# Sensors.net
KiCad netlist of a schematic drawn in Altium Designer
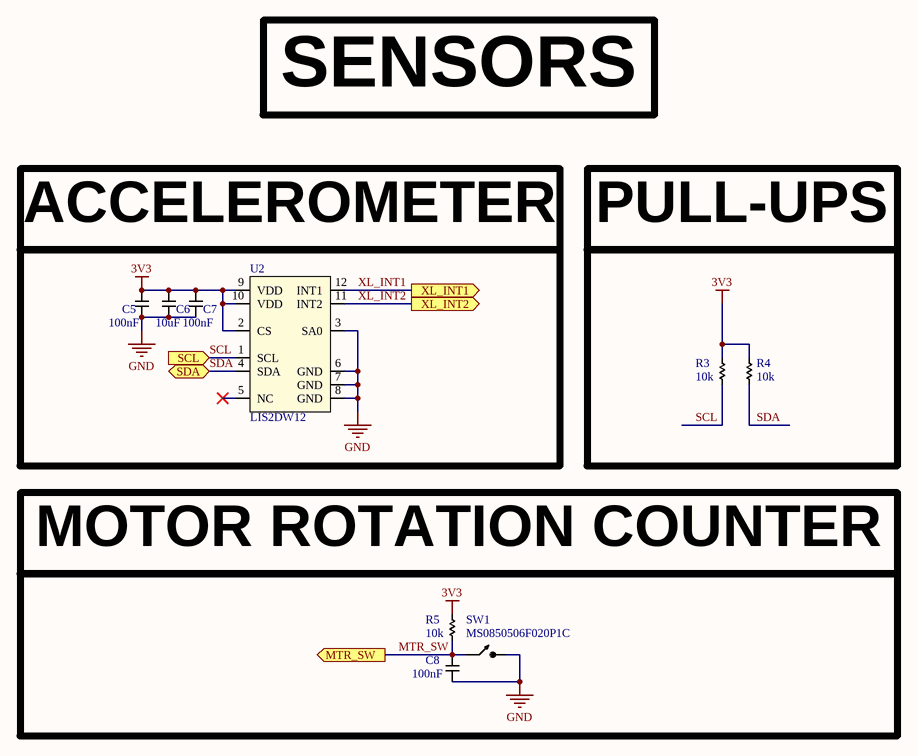
[diagram p0: Sensors.SchDoc]

(export (version "E")
  (design (tool "Eeschema 10.0.6"))
  (components
    (comp (ref "C5")
      (value "100nF")
      (footprint "CAP_0402_HIGH")
      (description "0402 Capacitor")
      (libsource (lib "smLib") (part "Capacitor_0402"))
    )
    (comp (ref "C6")
      (value "10uF")
      (footprint "CAP_0603_HIGH")
      (description "0603 Capacitor")
      (libsource (lib "smLib") (part "Capacitor_0603"))
    )
    (comp (ref "C7")
      (value "100nF")
      (footprint "CAP_0402_HIGH")
      (description "0402 Capacitor")
      (libsource (lib "smLib") (part "Capacitor_0402"))
    )
    (comp (ref "C8")
      (value "100nF")
      (footprint "CAP_0402_HIGH")
      (description "0402 Capacitor")
      (libsource (lib "smLib") (part "Capacitor_0402"))
    )
    (comp (ref "R3")
      (value "10k")
      (footprint "RES_0402_HIGH")
      (description "0402 Resistor")
      (libsource (lib "smLib") (part "Resistor_0402"))
    )
    (comp (ref "R4")
      (value "10k")
      (footprint "RES_0402_HIGH")
      (description "0402 Resistor")
      (libsource (lib "smLib") (part "Resistor_0402"))
    )
    (comp (ref "R5")
      (value "10k")
      (footprint "RES_0402_HIGH")
      (description "0402 Resistor")
      (libsource (lib "smLib") (part "Resistor_0402"))
    )
    (comp (ref "SW1")
      (value "MS0850506F020P1C")
      (footprint "MS0850506F020P1C")
      (description "MS0850506F020P1C SWITCH SNAP ACT SPST-NO 5A 125V")
      (libsource (lib "smLib") (part "MS0850506F020P1C"))
    )
    (comp (ref "U2")
      (value "LIS2DW12")
      (footprint "LIS2DW12")
      (description "LIS2DW12 Accelerometer X, Y, Z Axis ±2g, 4g, 8g, 16g 400Hz 12-LGA (2x2)")
      (libsource (lib "smLib") (part "LIS2DW12"))
    )
  )
  (nets
    (net (code "1") (name "/MTR_SW") (class "Default")
      (node (ref "C8") (pin "2") (pinfunction "2_2") (pintype "passive"))
      (node (ref "R5") (pin "1") (pinfunction "1_1") (pintype "passive"))
      (node (ref "SW1") (pin "1") (pinfunction "1_1") (pintype "passive"))
    )
    (net (code "2") (name "/SCL") (class "Default")
      (node (ref "R3") (pin "1") (pinfunction "1_1") (pintype "passive"))
      (node (ref "U2") (pin "1") (pinfunction "SCL_1") (pintype "passive"))
    )
    (net (code "3") (name "/SDA") (class "Default")
      (node (ref "R4") (pin "1") (pinfunction "1_1") (pintype "passive"))
      (node (ref "U2") (pin "4") (pinfunction "SDA_4") (pintype "passive"))
    )
    (net (code "4") (name "/XL_INT1") (class "Default")
      (node (ref "U2") (pin "12") (pinfunction "INT1_12") (pintype "passive"))
    )
    (net (code "5") (name "/XL_INT2") (class "Default")
      (node (ref "U2") (pin "11") (pinfunction "INT2_11") (pintype "passive"))
    )
    (net (code "6") (name "3V3") (class "Default")
      (node (ref "C5") (pin "2") (pinfunction "2_2") (pintype "passive"))
      (node (ref "C6") (pin "2") (pinfunction "2_2") (pintype "passive"))
      (node (ref "C7") (pin "2") (pinfunction "2_2") (pintype "passive"))
      (node (ref "R3") (pin "2") (pinfunction "2_2") (pintype "passive"))
      (node (ref "R4") (pin "2") (pinfunction "2_2") (pintype "passive"))
      (node (ref "R5") (pin "2") (pinfunction "2_2") (pintype "passive"))
      (node (ref "U2") (pin "10") (pinfunction "VDD_10") (pintype "passive"))
      (node (ref "U2") (pin "2") (pinfunction "CS_2") (pintype "passive"))
      (node (ref "U2") (pin "9") (pinfunction "VDD_9") (pintype "passive"))
    )
    (net (code "7") (name "GND") (class "Default")
      (node (ref "C5") (pin "1") (pinfunction "1_1") (pintype "passive"))
      (node (ref "C6") (pin "1") (pinfunction "1_1") (pintype "passive"))
      (node (ref "C7") (pin "1") (pinfunction "1_1") (pintype "passive"))
      (node (ref "C8") (pin "1") (pinfunction "1_1") (pintype "passive"))
      (node (ref "SW1") (pin "2") (pinfunction "2_2") (pintype "passive"))
      (node (ref "U2") (pin "3") (pinfunction "SA0_3") (pintype "passive"))
      (node (ref "U2") (pin "6") (pinfunction "GND_6") (pintype "passive"))
      (node (ref "U2") (pin "7") (pinfunction "GND_7") (pintype "passive"))
      (node (ref "U2") (pin "8") (pinfunction "GND_8") (pintype "passive"))
    )
    (net (code "8") (name "unconnected-(U2-NC-Pad5)") (class "Default")
      (node (ref "U2") (pin "5") (pinfunction "NC_5") (pintype "passive+no_connect"))
    )
  )
)
